# SCH_Hackaton_2023-12-24.net
KiCad netlist of a schematic drawn in EasyEDA
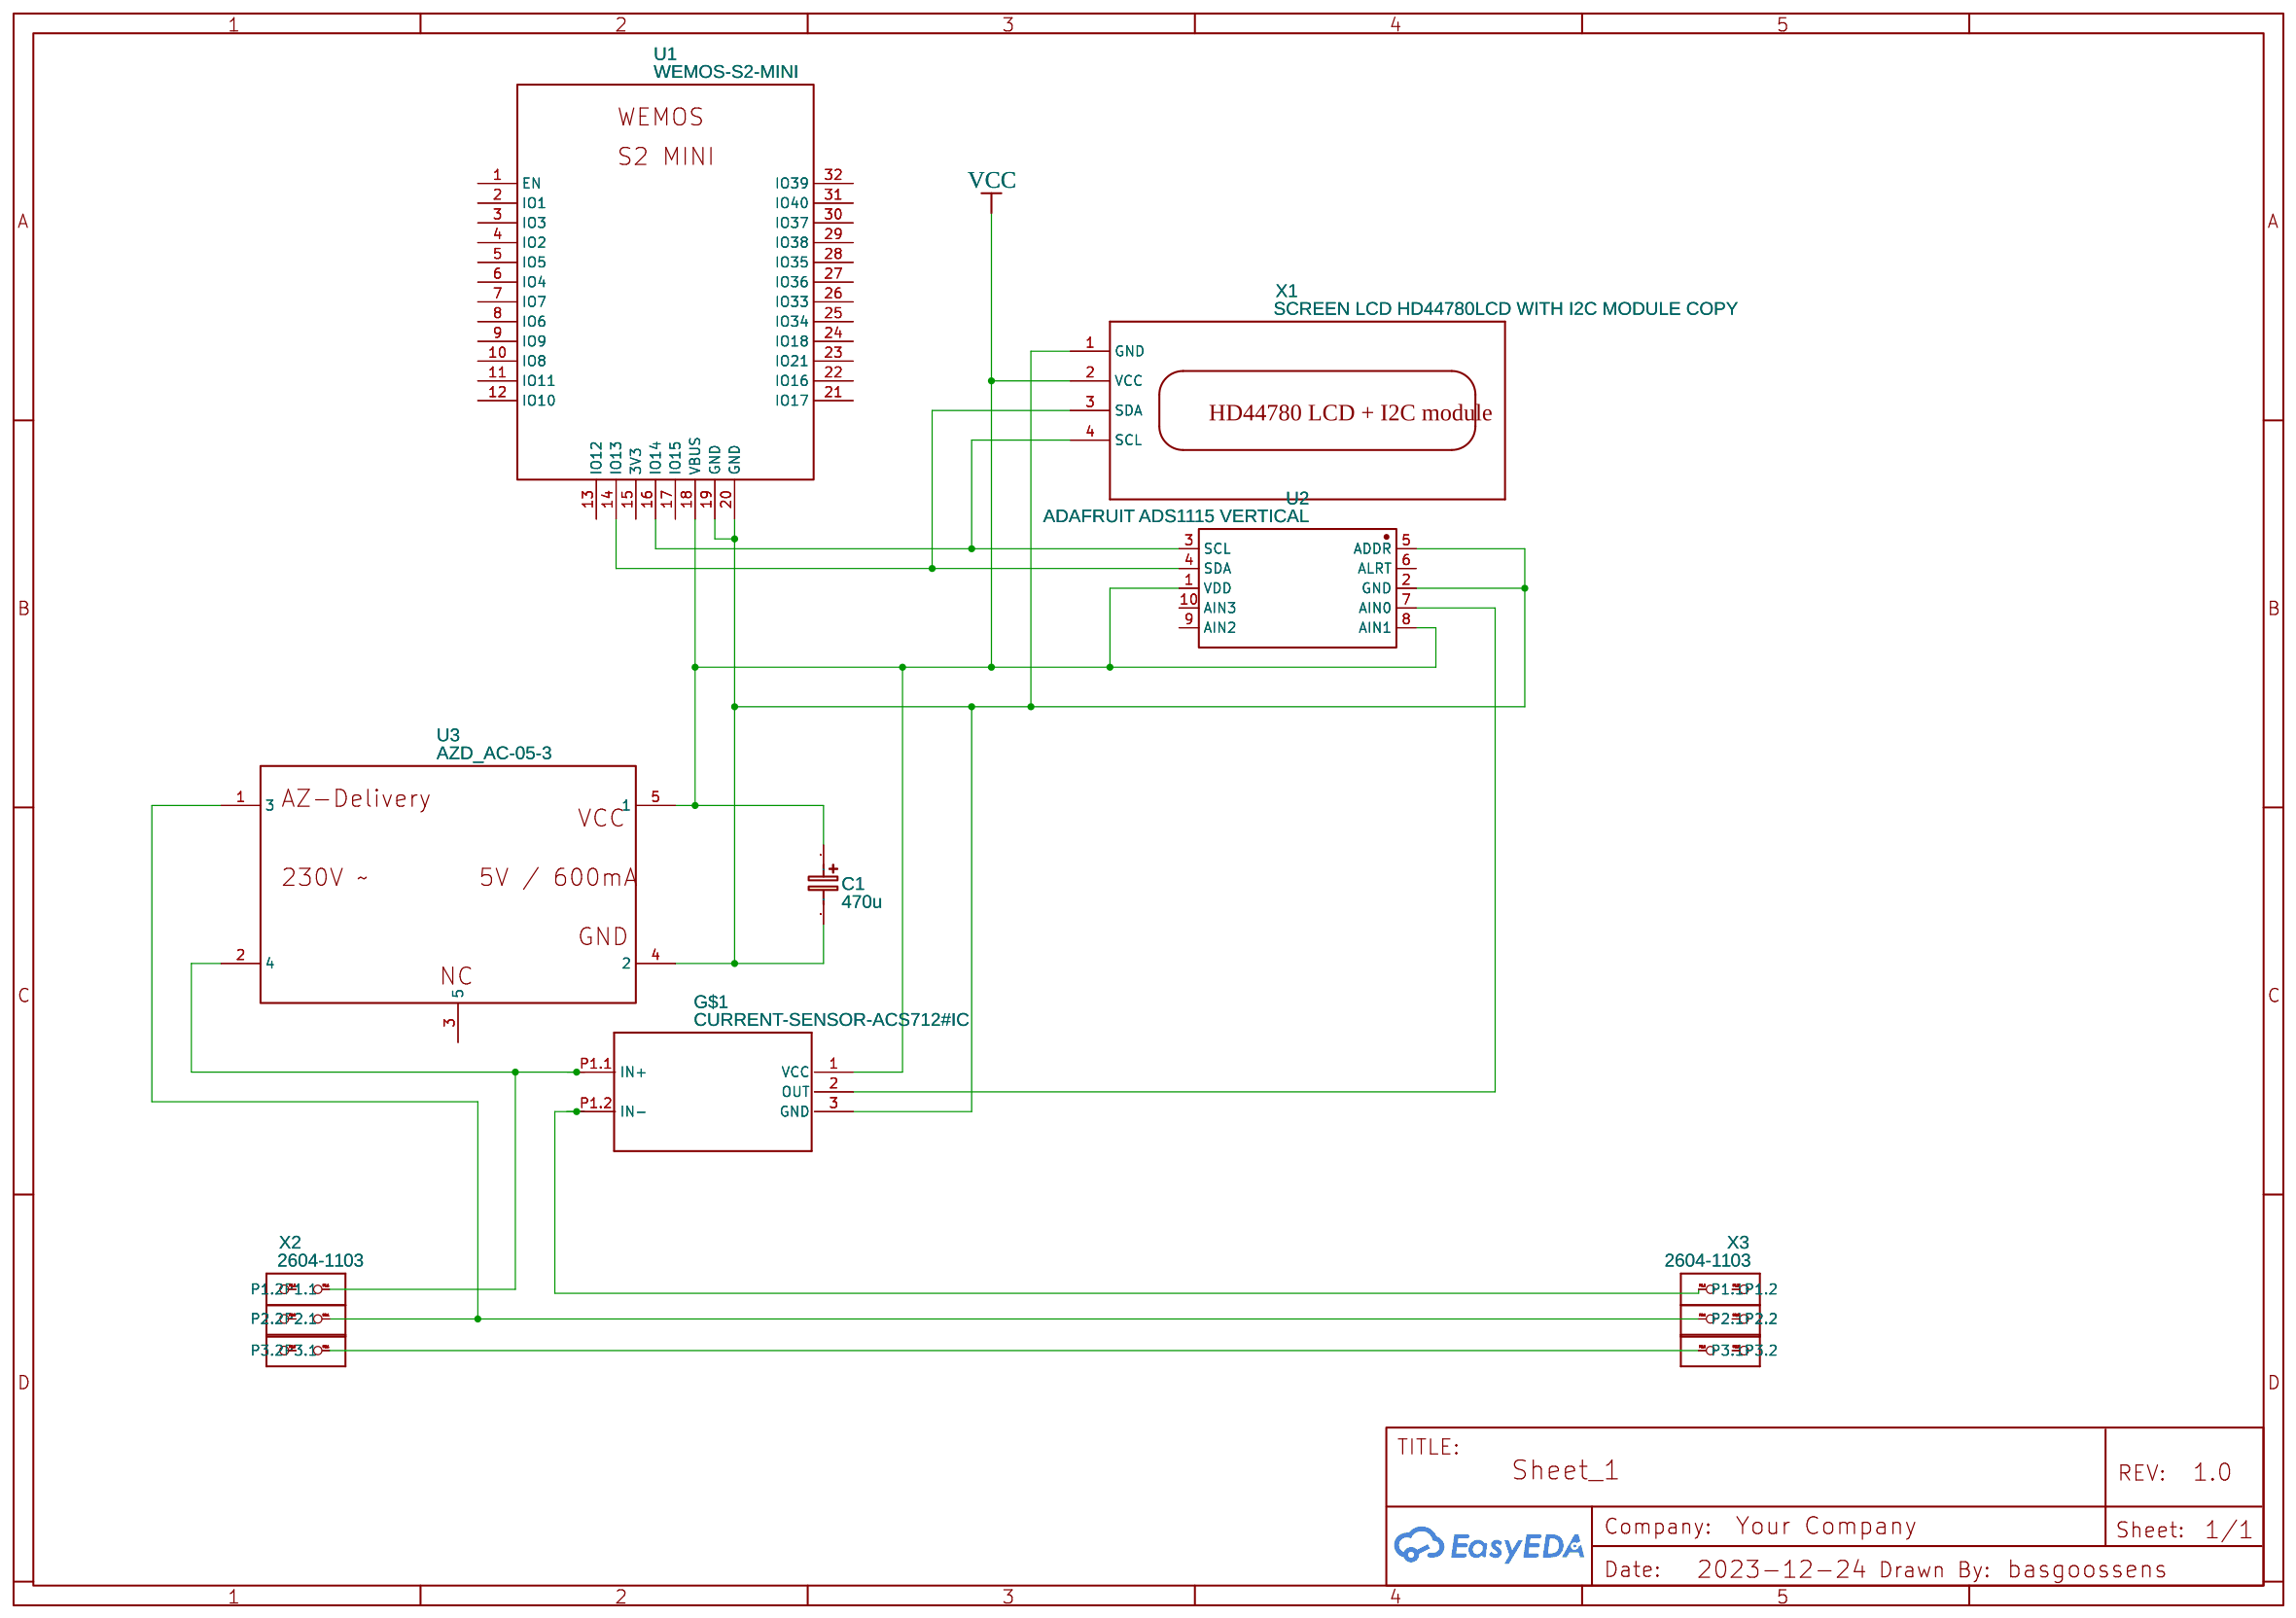
[diagram p0: schematic sheet]

(export (version "E")
  (design (tool "Eeschema 10.0.6"))
  (components
    (comp (ref "C1") (value "470u") (libsource (lib "") (part "CE_TH_D8.0×F3.5_EU")))
    (comp (ref "G$1")
      (value "CURRENT-SENSOR-ACS712#IC")
      (libsource (lib "") (part "CURRENT-SENSOR-ACS712#IC"))
    )
    (comp (ref "U1")
      (value "WEMOS-S2-MINI")
      (fields (field (name "Manufacturer Part") "Wemos") (field (name "Manufacturer") "WEMOS"))
      (libsource (lib "") (part "WEMOS-S2-MINI"))
    )
    (comp (ref "U2")
      (value "ADAFRUIT ADS1115 VERTICAL")
      (fields (field (name "Manufacturer Part") "ADS1115") (field (name "Manufacturer") "Texas Instruments"))
      (libsource (lib "") (part "ADAFRUIT ADS1115 VERTICAL"))
    )
    (comp (ref "U3")
      (value "AZD_AC-05-3")
      (fields (field (name "Manufacturer Part") "AC-05-3") (field (name "Manufacturer") "AZ-Delivery"))
      (libsource (lib "") (part "AZD_AC-05-3"))
    )
    (comp (ref "X1")
      (value "SCREEN LCD HD44780LCD WITH I2C MODULE COPY")
      (libsource (lib "") (part "SCREEN LCD HD44780LCD WITH I2C MODULE COPY"))
    )
    (comp (ref "X2") (value "2604-1103") (libsource (lib "") (part "2604-1103")))
    (comp (ref "X3") (value "2604-1103") (libsource (lib "") (part "2604-1103_1")))
  )
  (nets
    (net (code "1") (name "Net-(G$1-GND)") (class "Default")
      (node (ref "C1") (pin "2") (pinfunction "2_2") (pintype "unspecified"))
      (node (ref "G$1") (pin "3") (pinfunction "GND_3") (pintype "bidirectional"))
      (node (ref "U1") (pin "19") (pinfunction "GND_19") (pintype "passive"))
      (node (ref "U1") (pin "20") (pinfunction "GND_20") (pintype "passive"))
      (node (ref "U2") (pin "2") (pinfunction "GND_2") (pintype "unspecified"))
      (node (ref "U2") (pin "5") (pinfunction "ADDR_5") (pintype "unspecified"))
      (node (ref "U3") (pin "4") (pinfunction "2_4") (pintype "unspecified"))
      (node (ref "X1") (pin "1") (pinfunction "GND_1") (pintype "unspecified"))
    )
    (net (code "2") (name "Net-(G$1-IN+)") (class "Default")
      (node (ref "G$1") (pin "P1.1") (pinfunction "IN+_P1.1") (pintype "bidirectional"))
      (node (ref "U3") (pin "2") (pinfunction "4_2") (pintype "unspecified"))
      (node (ref "X2") (pin "P1.1") (pinfunction "P1.1_P1.1") (pintype "bidirectional"))
    )
    (net (code "3") (name "Net-(G$1-IN-)") (class "Default")
      (node (ref "G$1") (pin "P1.2") (pinfunction "IN-_P1.2") (pintype "bidirectional"))
      (node (ref "X3") (pin "P1.1") (pinfunction "P1.1_P1.1") (pintype "bidirectional"))
    )
    (net (code "4") (name "Net-(G$1-OUT)") (class "Default")
      (node (ref "G$1") (pin "2") (pinfunction "OUT_2") (pintype "bidirectional"))
      (node (ref "U2") (pin "7") (pinfunction "AIN0_7") (pintype "unspecified"))
    )
    (net (code "5") (name "Net-(U1-IO13)") (class "Default")
      (node (ref "U1") (pin "14") (pinfunction "IO13_14") (pintype "bidirectional"))
      (node (ref "U2") (pin "4") (pinfunction "SDA_4") (pintype "unspecified"))
      (node (ref "X1") (pin "3") (pinfunction "SDA_3") (pintype "unspecified"))
    )
    (net (code "6") (name "Net-(U1-IO14)") (class "Default")
      (node (ref "U1") (pin "16") (pinfunction "IO14_16") (pintype "bidirectional"))
      (node (ref "U2") (pin "3") (pinfunction "SCL_3") (pintype "unspecified"))
      (node (ref "X1") (pin "4") (pinfunction "SCL_4") (pintype "unspecified"))
    )
    (net (code "7") (name "Net-(U3-3)") (class "Default")
      (node (ref "U3") (pin "1") (pinfunction "3_1") (pintype "unspecified"))
      (node (ref "X2") (pin "P2.1") (pinfunction "P2.1_P2.1") (pintype "bidirectional"))
      (node (ref "X3") (pin "P2.1") (pinfunction "P2.1_P2.1") (pintype "bidirectional"))
    )
    (net (code "8") (name "Net-(X2-PadP3.1)") (class "Default")
      (node (ref "X2") (pin "P3.1") (pinfunction "P3.1_P3.1") (pintype "bidirectional"))
      (node (ref "X3") (pin "P3.1") (pinfunction "P3.1_P3.1") (pintype "bidirectional"))
    )
    (net (code "9") (name "VCC") (class "Default")
      (node (ref "C1") (pin "1") (pinfunction "1_1") (pintype "unspecified"))
      (node (ref "G$1") (pin "1") (pinfunction "VCC_1") (pintype "bidirectional"))
      (node (ref "U1") (pin "18") (pinfunction "VBUS_18") (pintype "bidirectional"))
      (node (ref "U2") (pin "1") (pinfunction "VDD_1") (pintype "unspecified"))
      (node (ref "U2") (pin "8") (pinfunction "AIN1_8") (pintype "unspecified"))
      (node (ref "U3") (pin "5") (pinfunction "1_5") (pintype "unspecified"))
      (node (ref "X1") (pin "2") (pinfunction "VCC_2") (pintype "unspecified"))
    )
    (net (code "10") (name "unconnected-(U1-3V3-Pad15)") (class "Default")
      (node (ref "U1") (pin "15") (pinfunction "3V3_15") (pintype "passive"))
    )
    (net (code "11") (name "unconnected-(U1-EN-Pad1)") (class "Default")
      (node (ref "U1") (pin "1") (pinfunction "EN_1") (pintype "input"))
    )
    (net (code "12") (name "unconnected-(U1-IO1-Pad2)") (class "Default")
      (node (ref "U1") (pin "2") (pinfunction "IO1_2") (pintype "bidirectional"))
    )
    (net (code "13") (name "unconnected-(U1-IO2-Pad4)") (class "Default")
      (node (ref "U1") (pin "4") (pinfunction "IO2_4") (pintype "bidirectional"))
    )
    (net (code "14") (name "unconnected-(U1-IO3-Pad3)") (class "Default")
      (node (ref "U1") (pin "3") (pinfunction "IO3_3") (pintype "bidirectional"))
    )
    (net (code "15") (name "unconnected-(U1-IO4-Pad6)") (class "Default")
      (node (ref "U1") (pin "6") (pinfunction "IO4_6") (pintype "bidirectional"))
    )
    (net (code "16") (name "unconnected-(U1-IO5-Pad5)") (class "Default")
      (node (ref "U1") (pin "5") (pinfunction "IO5_5") (pintype "bidirectional"))
    )
    (net (code "17") (name "unconnected-(U1-IO6-Pad8)") (class "Default")
      (node (ref "U1") (pin "8") (pinfunction "IO6_8") (pintype "bidirectional"))
    )
    (net (code "18") (name "unconnected-(U1-IO7-Pad7)") (class "Default")
      (node (ref "U1") (pin "7") (pinfunction "IO7_7") (pintype "bidirectional"))
    )
    (net (code "19") (name "unconnected-(U1-IO8-Pad10)") (class "Default")
      (node (ref "U1") (pin "10") (pinfunction "IO8_10") (pintype "bidirectional"))
    )
    (net (code "20") (name "unconnected-(U1-IO9-Pad9)") (class "Default")
      (node (ref "U1") (pin "9") (pinfunction "IO9_9") (pintype "bidirectional"))
    )
    (net (code "21") (name "unconnected-(U1-IO10-Pad12)") (class "Default")
      (node (ref "U1") (pin "12") (pinfunction "IO10_12") (pintype "bidirectional"))
    )
    (net (code "22") (name "unconnected-(U1-IO11-Pad11)") (class "Default")
      (node (ref "U1") (pin "11") (pinfunction "IO11_11") (pintype "bidirectional"))
    )
    (net (code "23") (name "unconnected-(U1-IO12-Pad13)") (class "Default")
      (node (ref "U1") (pin "13") (pinfunction "IO12_13") (pintype "bidirectional"))
    )
    (net (code "24") (name "unconnected-(U1-IO15-Pad17)") (class "Default")
      (node (ref "U1") (pin "17") (pinfunction "IO15_17") (pintype "bidirectional"))
    )
    (net (code "25") (name "unconnected-(U1-IO16-Pad22)") (class "Default")
      (node (ref "U1") (pin "22") (pinfunction "IO16_22") (pintype "passive"))
    )
    (net (code "26") (name "unconnected-(U1-IO17-Pad21)") (class "Default")
      (node (ref "U1") (pin "21") (pinfunction "IO17_21") (pintype "passive"))
    )
    (net (code "27") (name "unconnected-(U1-IO18-Pad24)") (class "Default")
      (node (ref "U1") (pin "24") (pinfunction "IO18_24") (pintype "passive"))
    )
    (net (code "28") (name "unconnected-(U1-IO21-Pad23)") (class "Default")
      (node (ref "U1") (pin "23") (pinfunction "IO21_23") (pintype "passive"))
    )
    (net (code "29") (name "unconnected-(U1-IO33-Pad26)") (class "Default")
      (node (ref "U1") (pin "26") (pinfunction "IO33_26") (pintype "passive"))
    )
    (net (code "30") (name "unconnected-(U1-IO34-Pad25)") (class "Default")
      (node (ref "U1") (pin "25") (pinfunction "IO34_25") (pintype "passive"))
    )
    (net (code "31") (name "unconnected-(U1-IO35-Pad28)") (class "Default")
      (node (ref "U1") (pin "28") (pinfunction "IO35_28") (pintype "passive"))
    )
    (net (code "32") (name "unconnected-(U1-IO36-Pad27)") (class "Default")
      (node (ref "U1") (pin "27") (pinfunction "IO36_27") (pintype "passive"))
    )
    (net (code "33") (name "unconnected-(U1-IO37-Pad30)") (class "Default")
      (node (ref "U1") (pin "30") (pinfunction "IO37_30") (pintype "passive"))
    )
    (net (code "34") (name "unconnected-(U1-IO38-Pad29)") (class "Default")
      (node (ref "U1") (pin "29") (pinfunction "IO38_29") (pintype "passive"))
    )
    (net (code "35") (name "unconnected-(U1-IO39-Pad32)") (class "Default")
      (node (ref "U1") (pin "32") (pinfunction "IO39_32") (pintype "passive"))
    )
    (net (code "36") (name "unconnected-(U1-IO40-Pad31)") (class "Default")
      (node (ref "U1") (pin "31") (pinfunction "IO40_31") (pintype "passive"))
    )
    (net (code "37") (name "unconnected-(U2-AIN2-Pad9)") (class "Default")
      (node (ref "U2") (pin "9") (pinfunction "AIN2_9") (pintype "unspecified"))
    )
    (net (code "38") (name "unconnected-(U2-AIN3-Pad10)") (class "Default")
      (node (ref "U2") (pin "10") (pinfunction "AIN3_10") (pintype "unspecified"))
    )
    (net (code "39") (name "unconnected-(U2-ALRT-Pad6)") (class "Default")
      (node (ref "U2") (pin "6") (pinfunction "ALRT_6") (pintype "unspecified"))
    )
    (net (code "40") (name "unconnected-(U3-5-Pad3)") (class "Default")
      (node (ref "U3") (pin "3") (pinfunction "5_3") (pintype "unspecified"))
    )
    (net (code "41") (name "unconnected-(X2-PadP1.2)") (class "Default")
      (node (ref "X2") (pin "P1.2") (pinfunction "P1.2_P1.2") (pintype "bidirectional"))
    )
    (net (code "42") (name "unconnected-(X2-PadP2.2)") (class "Default")
      (node (ref "X2") (pin "P2.2") (pinfunction "P2.2_P2.2") (pintype "bidirectional"))
    )
    (net (code "43") (name "unconnected-(X2-PadP3.2)") (class "Default")
      (node (ref "X2") (pin "P3.2") (pinfunction "P3.2_P3.2") (pintype "bidirectional"))
    )
    (net (code "44") (name "unconnected-(X3-PadP1.2)") (class "Default")
      (node (ref "X3") (pin "P1.2") (pinfunction "P1.2_P1.2") (pintype "bidirectional"))
    )
    (net (code "45") (name "unconnected-(X3-PadP2.2)") (class "Default")
      (node (ref "X3") (pin "P2.2") (pinfunction "P2.2_P2.2") (pintype "bidirectional"))
    )
    (net (code "46") (name "unconnected-(X3-PadP3.2)") (class "Default")
      (node (ref "X3") (pin "P3.2") (pinfunction "P3.2_P3.2") (pintype "bidirectional"))
    )
  )
)
